# SparkFun_NanoBeacon_Board_-_IN100.net
KiCad netlist of a schematic drawn in EAGLE
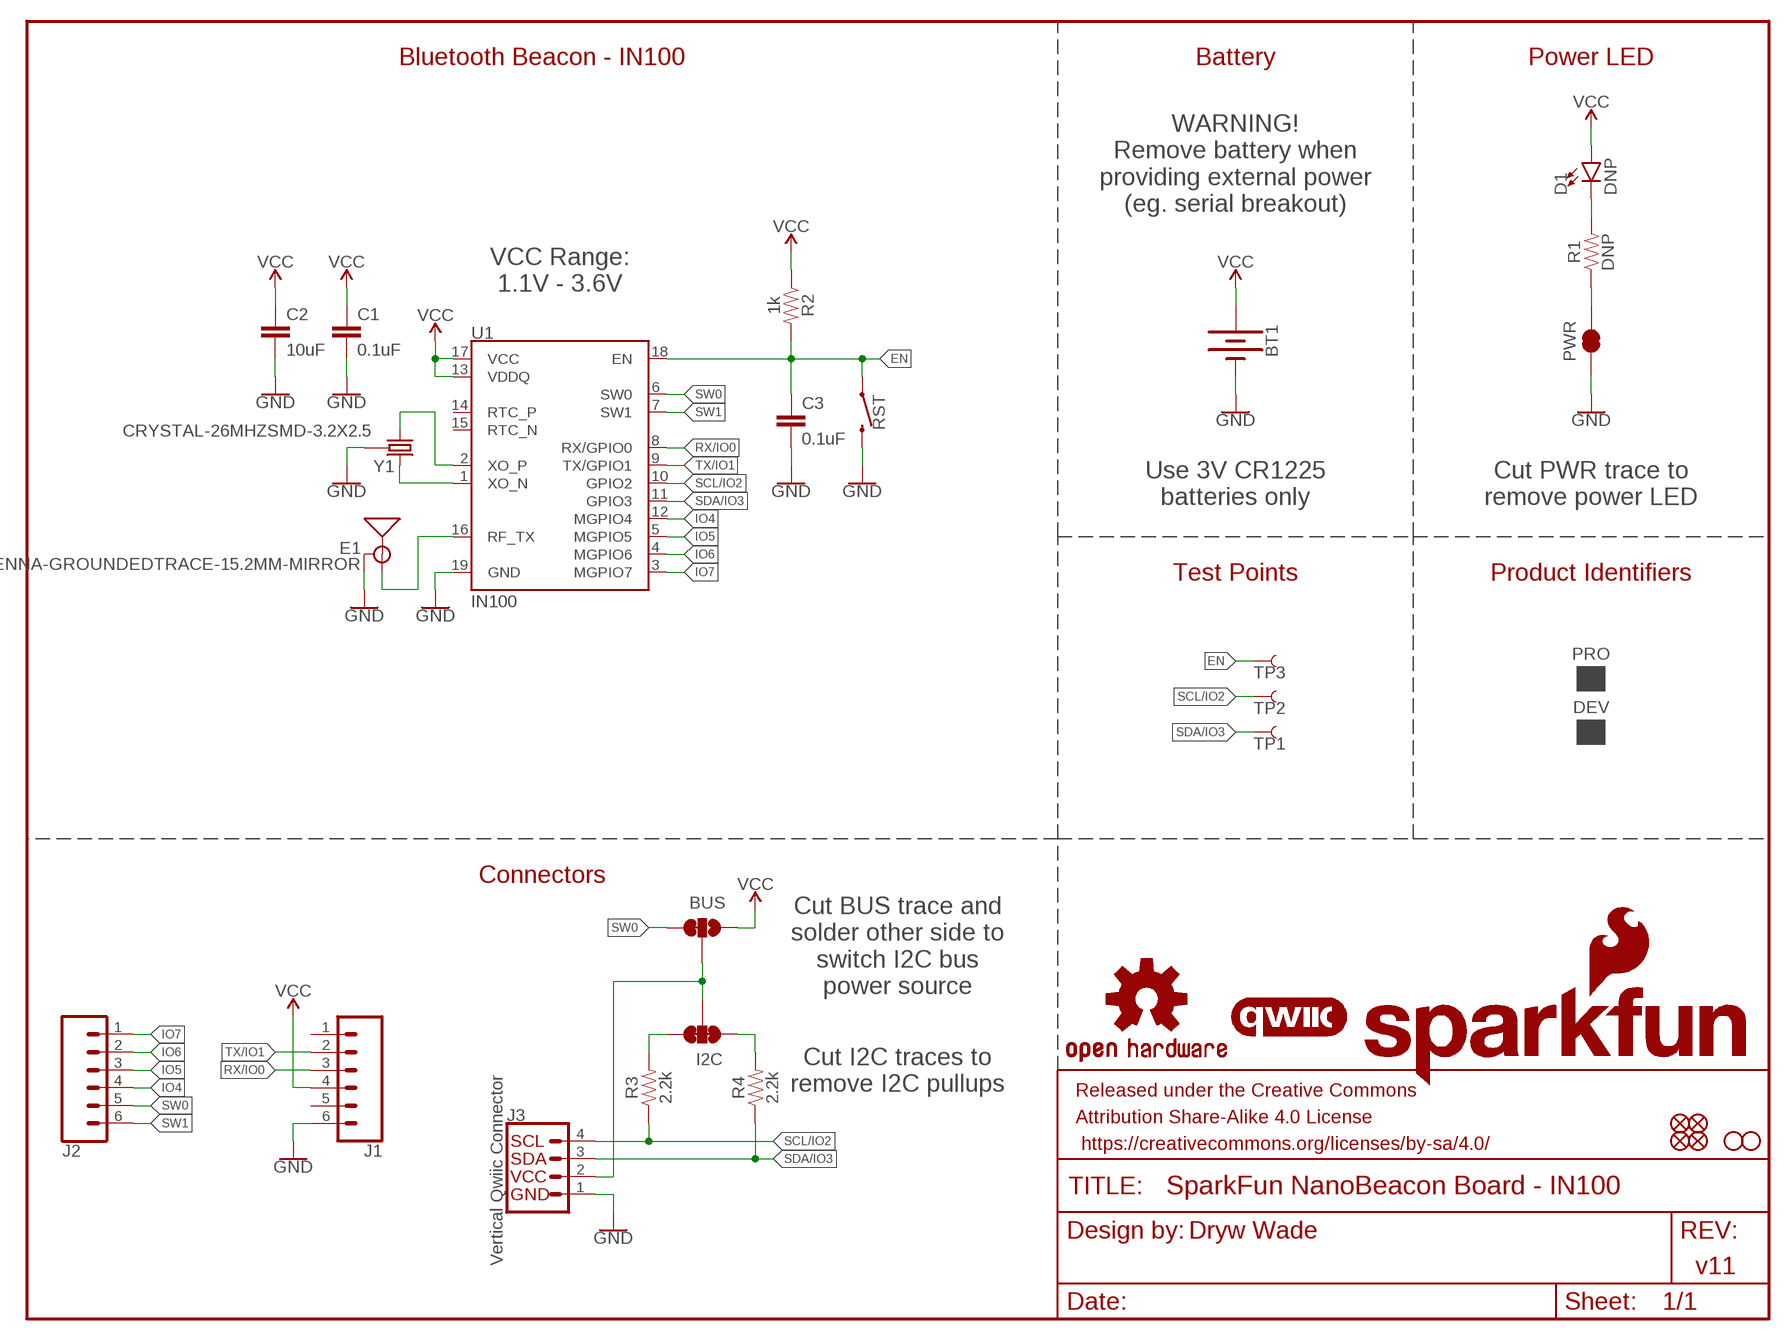
[diagram p0: schematic, sheet 1]

(export (version "E")
  (design (tool "Eeschema 10.0.6"))
  (components
    (comp (ref "BT1")
      (value "BATTERY-12MM_SMD_BOTH_PWR_PADS")
      (footprint "eagle-import:BATTCON_12MM")
      (libsource (lib "eagle-import") (part "BATTERY-12MM_SMD_BOTH_PWR_PADS"))
    )
    (comp (ref "BUS")
      (value "JUMPER-SMT_3_1-NC_TRACE_SILK")
      (footprint "eagle-import:SMT-JUMPER_3_1-NC_TRACE_SILK")
      (libsource (lib "eagle-import") (part "JUMPER-SMT_3_1-NC_TRACE_SILK"))
    )
    (comp (ref "C1")
      (value "0.1uF")
      (footprint "eagle-import:0402-TIGHT")
      (libsource (lib "eagle-import") (part "0.1UF-0402T-6.3V-10%-X7R"))
    )
    (comp (ref "C2")
      (value "10uF")
      (footprint "eagle-import:0402-TIGHT")
      (libsource (lib "eagle-import") (part "10UF-0402T-6.3V-20%"))
    )
    (comp (ref "C3")
      (value "0.1uF")
      (footprint "eagle-import:0402-TIGHT")
      (libsource (lib "eagle-import") (part "0.1UF-0402T-6.3V-10%-X7R"))
    )
    (comp (ref "D1")
      (value "DNP")
      (footprint "eagle-import:LED-0402")
      (libsource (lib "eagle-import") (part "LED-RED_0402"))
    )
    (comp (ref "DEV")
      (value "PROD_ID_PASTE_SILK")
      (footprint "eagle-import:PRODUCT_IDENT_PASTE_SILK")
      (libsource (lib "eagle-import") (part "PROD_ID_PASTE_SILK"))
    )
    (comp (ref "E1")
      (value "ANTENNA-GROUNDEDTRACE-15.2MM-MIRROR")
      (footprint "eagle-import:TRACE_ANTENNA_2.4GHZ_15.2MM_MIRROR")
      (libsource (lib "eagle-import") (part "ANTENNA-GROUNDEDTRACE-15.2MM-MIRROR"))
    )
    (comp (ref "FD1")
      (value "FIDUCIAL1X2")
      (footprint "eagle-import:FIDUCIAL-1X2")
      (libsource (lib "eagle-import") (part "FIDUCIAL1X2"))
    )
    (comp (ref "FD2")
      (value "FIDUCIAL1X2")
      (footprint "eagle-import:FIDUCIAL-1X2")
      (libsource (lib "eagle-import") (part "FIDUCIAL1X2"))
    )
    (comp (ref "FD3")
      (value "FIDUCIAL1X2")
      (footprint "eagle-import:FIDUCIAL-1X2")
      (libsource (lib "eagle-import") (part "FIDUCIAL1X2"))
    )
    (comp (ref "FD4")
      (value "FIDUCIAL1X2")
      (footprint "eagle-import:FIDUCIAL-1X2")
      (libsource (lib "eagle-import") (part "FIDUCIAL1X2"))
    )
    (comp (ref "FRAME1")
      (value "FRAME-LETTER")
      (footprint "eagle-import:CREATIVE_COMMONS")
      (libsource (lib "eagle-import") (part "FRAME-LETTER"))
    )
    (comp (ref "H1")
      (value "STAND-OFF")
      (footprint "eagle-import:STAND-OFF")
      (libsource (lib "eagle-import") (part "STAND-OFF"))
    )
    (comp (ref "H2")
      (value "STAND-OFF")
      (footprint "eagle-import:STAND-OFF")
      (libsource (lib "eagle-import") (part "STAND-OFF"))
    )
    (comp (ref "I2C")
      (value "JUMPER-SMT_3_2-NC_TRACE_SILK")
      (footprint "eagle-import:SMT-JUMPER_3_2-NC_TRACE_SILK")
      (libsource (lib "eagle-import") (part "JUMPER-SMT_3_2-NC_TRACE_SILK"))
    )
    (comp (ref "J1")
      (value "CONN_06NO_SILK_NO_POP")
      (footprint "eagle-import:1X06_NO_SILK")
      (libsource (lib "eagle-import") (part "CONN_06NO_SILK_NO_POP"))
    )
    (comp (ref "J2")
      (value "CONN_06NO_SILK_NO_POP")
      (footprint "eagle-import:1X06_NO_SILK")
      (libsource (lib "eagle-import") (part "CONN_06NO_SILK_NO_POP"))
    )
    (comp (ref "J3")
      (value "Vertical Qwiic Connector")
      (footprint "eagle-import:JST04_1MM_VERT")
      (libsource (lib "eagle-import") (part "QWIIC_CONNECTOR"))
    )
    (comp (ref "LOGO1")
      (value "OSHW-LOGOS")
      (footprint "eagle-import:OSHW-LOGO-S")
      (libsource (lib "eagle-import") (part "OSHW-LOGOS"))
    )
    (comp (ref "LOGO2")
      (value "SFE_LOGO_NAME_FLAME.1_INCH")
      (footprint "eagle-import:SFE_LOGO_NAME_FLAME_.1")
      (libsource (lib "eagle-import") (part "SFE_LOGO_NAME_FLAME.1_INCH"))
    )
    (comp (ref "LOGO3")
      (value "QWIIC_LOGO_5MM")
      (footprint "eagle-import:QWIIC_5MM")
      (libsource (lib "eagle-import") (part "QWIIC_LOGO_5MM"))
    )
    (comp (ref "PRO")
      (value "PROD_ID_PASTE_SILK")
      (footprint "eagle-import:PRODUCT_IDENT_PASTE_SILK")
      (libsource (lib "eagle-import") (part "PROD_ID_PASTE_SILK"))
    )
    (comp (ref "PWR")
      (value "JUMPER-SMT_2_NC_TRACE_SILK")
      (footprint "eagle-import:SMT-JUMPER_2_NC_TRACE_SILK")
      (libsource (lib "eagle-import") (part "JUMPER-SMT_2_NC_TRACE_SILK"))
    )
    (comp (ref "R1")
      (value "DNP")
      (footprint "eagle-import:0402-TIGHT")
      (libsource (lib "eagle-import") (part "2.2KOHM-0402T-1/16W-1%"))
    )
    (comp (ref "R2")
      (value "1k")
      (footprint "eagle-import:0402-TIGHT")
      (libsource (lib "eagle-import") (part "1KOHM-0402T-1/16W-1%"))
    )
    (comp (ref "R3")
      (value "2.2k")
      (footprint "eagle-import:0402-TIGHT")
      (libsource (lib "eagle-import") (part "2.2KOHM-0402T-1/16W-1%"))
    )
    (comp (ref "R4")
      (value "2.2k")
      (footprint "eagle-import:0402-TIGHT")
      (libsource (lib "eagle-import") (part "2.2KOHM-0402T-1/16W-1%"))
    )
    (comp (ref "RST")
      (value "DNP")
      (footprint "eagle-import:TACTILE_SWITCH_SMD_4.6X2.8MM")
      (libsource (lib "eagle-import") (part "MOMENTARY-SWITCH-SPST-SMD-4.6X2.8MM"))
    )
    (comp (ref "TP1")
      (value "TEST-POINT3")
      (footprint "eagle-import:PAD.03X.03")
      (libsource (lib "eagle-import") (part "TEST-POINT3"))
    )
    (comp (ref "TP2")
      (value "TEST-POINT3")
      (footprint "eagle-import:PAD.03X.03")
      (libsource (lib "eagle-import") (part "TEST-POINT3"))
    )
    (comp (ref "TP3")
      (value "TEST-POINT3")
      (footprint "eagle-import:PAD.03X.03")
      (libsource (lib "eagle-import") (part "TEST-POINT3"))
    )
    (comp (ref "U1")
      (value "IN100")
      (footprint "eagle-import:IN100")
      (libsource (lib "eagle-import") (part "IN100"))
    )
    (comp (ref "Y1")
      (value "CRYSTAL-26MHZSMD-3.2X2.5")
      (footprint "eagle-import:CRYSTAL-SMD-3.2X2.5MM")
      (libsource (lib "eagle-import") (part "CRYSTAL-26MHZSMD-3.2X2.5"))
    )
  )
  (nets
    (net (code "1") (name "EN") (class "Default")
      (node (ref "C3") (pin "1") (pinfunction "1_1") (pintype "passive"))
      (node (ref "R2") (pin "2") (pinfunction "2_2") (pintype "passive"))
      (node (ref "RST") (pin "1") (pinfunction "1_1") (pintype "passive"))
      (node (ref "RST") (pin "2") (pinfunction "1_2") (pintype "passive"))
      (node (ref "TP3") (pin "1") (pinfunction "1_1") (pintype "bidirectional"))
      (node (ref "U1") (pin "18") (pinfunction "EN_18") (pintype "input"))
    )
    (net (code "2") (name "GND") (class "Default")
      (node (ref "BT1") (pin "GND") (pinfunction "-_GND") (pintype "power_in"))
      (node (ref "C1") (pin "2") (pinfunction "2_2") (pintype "passive"))
      (node (ref "C2") (pin "2") (pinfunction "2_2") (pintype "passive"))
      (node (ref "C3") (pin "2") (pinfunction "2_2") (pintype "passive"))
      (node (ref "E1") (pin "GND") (pinfunction "GND_GND") (pintype "bidirectional"))
      (node (ref "J1") (pin "6") (pinfunction "6_6") (pintype "passive"))
      (node (ref "J3") (pin "1") (pinfunction "1_1") (pintype "power_in"))
      (node (ref "PWR") (pin "1") (pinfunction "1_1") (pintype "passive"))
      (node (ref "RST") (pin "3") (pinfunction "2_3") (pintype "passive"))
      (node (ref "RST") (pin "4") (pinfunction "2_4") (pintype "passive"))
      (node (ref "U1") (pin "19") (pinfunction "GND_19") (pintype "power_in"))
      (node (ref "Y1") (pin "2") (pinfunction "GND_2") (pintype "power_in"))
      (node (ref "Y1") (pin "4") (pinfunction "GND_4") (pintype "power_in"))
    )
    (net (code "3") (name "IO4") (class "Default")
      (node (ref "J2") (pin "4") (pinfunction "4_4") (pintype "passive"))
      (node (ref "U1") (pin "12") (pinfunction "MGPIO4_12") (pintype "bidirectional"))
    )
    (net (code "4") (name "IO5") (class "Default")
      (node (ref "J2") (pin "3") (pinfunction "3_3") (pintype "passive"))
      (node (ref "U1") (pin "5") (pinfunction "MGPIO5_5") (pintype "bidirectional"))
    )
    (net (code "5") (name "IO6") (class "Default")
      (node (ref "J2") (pin "2") (pinfunction "2_2") (pintype "passive"))
      (node (ref "U1") (pin "4") (pinfunction "MGPIO6_4") (pintype "bidirectional"))
    )
    (net (code "6") (name "IO7") (class "Default")
      (node (ref "J2") (pin "1") (pinfunction "1_1") (pintype "passive"))
      (node (ref "U1") (pin "3") (pinfunction "MGPIO7_3") (pintype "bidirectional"))
    )
    (net (code "7") (name "Net-(BUS-Pad2)") (class "Default")
      (node (ref "BUS") (pin "2") (pinfunction "2_2") (pintype "passive"))
      (node (ref "I2C") (pin "2") (pinfunction "2_2") (pintype "passive"))
      (node (ref "J3") (pin "2") (pinfunction "2_2") (pintype "power_in"))
    )
    (net (code "8") (name "Net-(D1-PadC)") (class "Default")
      (node (ref "D1") (pin "C") (pinfunction "C_C") (pintype "passive"))
      (node (ref "R1") (pin "2") (pinfunction "2_2") (pintype "passive"))
    )
    (net (code "9") (name "Net-(E1-SIGNAL)") (class "Default")
      (node (ref "E1") (pin "ANT") (pinfunction "SIGNAL_ANT") (pintype "bidirectional"))
      (node (ref "U1") (pin "16") (pinfunction "RF_TX_16") (pintype "bidirectional"))
    )
    (net (code "10") (name "Net-(I2C-Pad1)") (class "Default")
      (node (ref "I2C") (pin "1") (pinfunction "1_1") (pintype "passive"))
      (node (ref "R4") (pin "2") (pinfunction "2_2") (pintype "passive"))
    )
    (net (code "11") (name "Net-(I2C-Pad3)") (class "Default")
      (node (ref "I2C") (pin "3") (pinfunction "3_3") (pintype "passive"))
      (node (ref "R3") (pin "2") (pinfunction "2_2") (pintype "passive"))
    )
    (net (code "12") (name "Net-(PWR-Pad2)") (class "Default")
      (node (ref "PWR") (pin "2") (pinfunction "2_2") (pintype "passive"))
      (node (ref "R1") (pin "1") (pinfunction "1_1") (pintype "passive"))
    )
    (net (code "13") (name "Net-(U1-XO_N)") (class "Default")
      (node (ref "U1") (pin "1") (pinfunction "XO_N_1") (pintype "bidirectional"))
      (node (ref "Y1") (pin "3") (pinfunction "2_3") (pintype "passive"))
    )
    (net (code "14") (name "Net-(U1-XO_P)") (class "Default")
      (node (ref "U1") (pin "2") (pinfunction "XO_P_2") (pintype "bidirectional"))
      (node (ref "Y1") (pin "1") (pinfunction "1_1") (pintype "passive"))
    )
    (net (code "15") (name "RX{slash}IO0") (class "Default")
      (node (ref "J1") (pin "3") (pinfunction "3_3") (pintype "passive"))
      (node (ref "U1") (pin "8") (pinfunction "RX/GPIO0_8") (pintype "bidirectional"))
    )
    (net (code "16") (name "SCL{slash}IO2") (class "Default")
      (node (ref "J3") (pin "4") (pinfunction "4_4") (pintype "passive"))
      (node (ref "R3") (pin "1") (pinfunction "1_1") (pintype "passive"))
      (node (ref "TP2") (pin "1") (pinfunction "1_1") (pintype "bidirectional"))
      (node (ref "U1") (pin "10") (pinfunction "GPIO2_10") (pintype "bidirectional"))
    )
    (net (code "17") (name "SDA{slash}IO3") (class "Default")
      (node (ref "J3") (pin "3") (pinfunction "3_3") (pintype "passive"))
      (node (ref "R4") (pin "1") (pinfunction "1_1") (pintype "passive"))
      (node (ref "TP1") (pin "1") (pinfunction "1_1") (pintype "bidirectional"))
      (node (ref "U1") (pin "11") (pinfunction "GPIO3_11") (pintype "bidirectional"))
    )
    (net (code "18") (name "SW0") (class "Default")
      (node (ref "BUS") (pin "3") (pinfunction "3_3") (pintype "passive"))
      (node (ref "J2") (pin "5") (pinfunction "5_5") (pintype "passive"))
      (node (ref "U1") (pin "6") (pinfunction "SW0_6") (pintype "output"))
    )
    (net (code "19") (name "SW1") (class "Default")
      (node (ref "J2") (pin "6") (pinfunction "6_6") (pintype "passive"))
      (node (ref "U1") (pin "7") (pinfunction "SW1_7") (pintype "output"))
    )
    (net (code "20") (name "TX{slash}IO1") (class "Default")
      (node (ref "J1") (pin "2") (pinfunction "2_2") (pintype "passive"))
      (node (ref "U1") (pin "9") (pinfunction "TX/GPIO1_9") (pintype "bidirectional"))
    )
    (net (code "21") (name "VCC") (class "Default")
      (node (ref "BT1") (pin "PWR@1") (pinfunction "+_PWR@1") (pintype "power_in"))
      (node (ref "BT1") (pin "PWR@2") (pinfunction "+_PWR@2") (pintype "power_in"))
      (node (ref "BUS") (pin "1") (pinfunction "1_1") (pintype "passive"))
      (node (ref "C1") (pin "1") (pinfunction "1_1") (pintype "passive"))
      (node (ref "C2") (pin "1") (pinfunction "1_1") (pintype "passive"))
      (node (ref "D1") (pin "A") (pinfunction "A_A") (pintype "passive"))
      (node (ref "J1") (pin "4") (pinfunction "4_4") (pintype "passive"))
      (node (ref "R2") (pin "1") (pinfunction "1_1") (pintype "passive"))
      (node (ref "U1") (pin "13") (pinfunction "VDDQ_13") (pintype "power_in"))
      (node (ref "U1") (pin "17") (pinfunction "VCC_17") (pintype "power_in"))
    )
    (net (code "22") (name "unconnected-(J1-Pad1)") (class "Default")
      (node (ref "J1") (pin "1") (pinfunction "1_1") (pintype "passive"))
    )
    (net (code "23") (name "unconnected-(J1-Pad5)") (class "Default")
      (node (ref "J1") (pin "5") (pinfunction "5_5") (pintype "passive"))
    )
    (net (code "24") (name "unconnected-(U1-RTC_N-Pad15)") (class "Default")
      (node (ref "U1") (pin "15") (pinfunction "RTC_N_15") (pintype "bidirectional"))
    )
    (net (code "25") (name "unconnected-(U1-RTC_P-Pad14)") (class "Default")
      (node (ref "U1") (pin "14") (pinfunction "RTC_P_14") (pintype "bidirectional"))
    )
  )
)
